# CANFD_SIC_transciever_with_WAKE_and_SLEE.net
KiCad netlist of a schematic drawn in Altium Designer
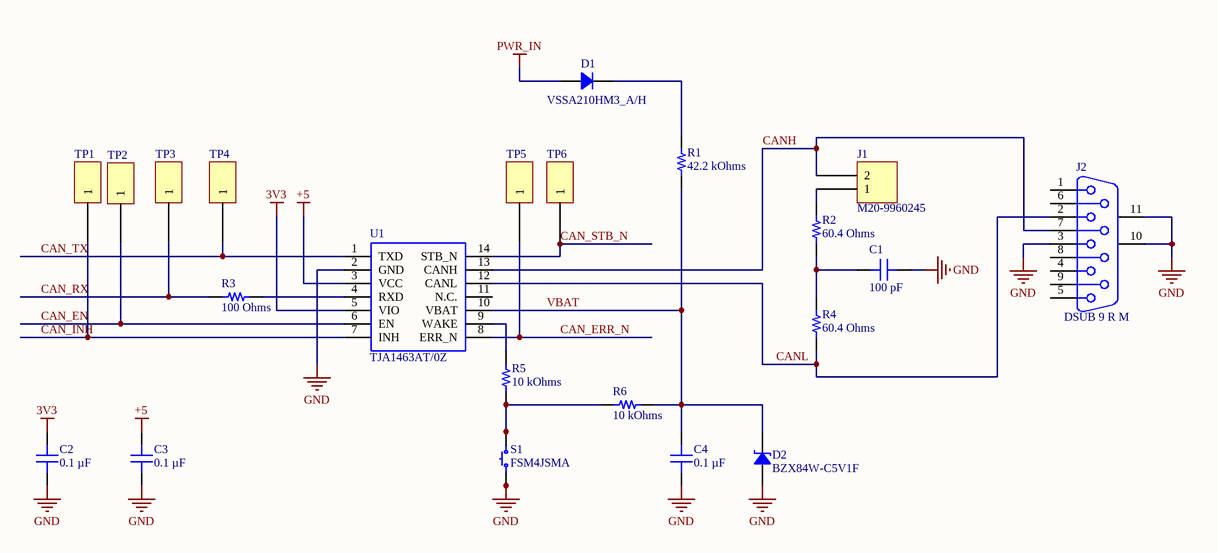
[diagram p0: CANFD_SIC_transciever_with_WAKE_and_SLEEP.SchDoc]

(export (version "E")
  (design (tool "Eeschema 10.0.6"))
  (components
    (comp (ref "C1")
      (value "100 pF")
      (footprint "CAP 0603_1608")
      (description "CAP CER 100PF 100V C0G/NPO 0603")
      (fields (field (name "PART NUMBER") "CC0603JRNPO0BN101") (field (name "MANUFACTURER") "Yageo"))
      (libsource (lib "Celestial Altium Library - altium_library") (part "Capacitor"))
    )
    (comp (ref "C2")
      (value "0.1 µF")
      (footprint "CAP 0603_1608")
      (description "CAP CER 0.1UF 16V X7R 0603")
      (fields (field (name "PART NUMBER") "CS0603KRX7R7BB104") (field (name "MANUFACTURER") "Yageo"))
      (libsource (lib "Celestial Altium Library - altium_library") (part "Capacitor"))
    )
    (comp (ref "C3")
      (value "0.1 µF")
      (footprint "CAP 0603_1608")
      (description "CAP CER 0.1UF 16V X7R 0603")
      (fields (field (name "PART NUMBER") "CS0603KRX7R7BB104") (field (name "MANUFACTURER") "Yageo"))
      (libsource (lib "Celestial Altium Library - altium_library") (part "Capacitor"))
    )
    (comp (ref "C4")
      (value "0.1 µF")
      (footprint "CAP 0603_1608")
      (description "CAP CER 0.1UF 16V X7R 0603")
      (fields (field (name "PART NUMBER") "CS0603KRX7R7BB104") (field (name "MANUFACTURER") "Yageo"))
      (libsource (lib "Celestial Altium Library - altium_library") (part "Capacitor"))
    )
    (comp (ref "D1")
      (value "VSSA210HM3_A/H")
      (footprint "DO214AC SMA")
      (description "DIODE SCHOTTKY 100V 2A DO214AC")
      (fields (field (name "MANUFACTURER") "Vishay Semiconductor Diodes Division"))
      (libsource (lib "Celestial Altium Library - altium_library") (part "Diode"))
    )
    (comp (ref "D2")
      (value "BZX84W-C5V1F")
      (footprint "DIODES SOT-323-3")
      (description "DIODE ZENER 5.1V 275MW SOT323")
      (fields (field (name "MANUFACTURER") "Nexperia USA Inc.") (field (name "TOLERANCE") "±5%"))
      (libsource (lib "Celestial Altium Library - altium_library") (part "Diode Zener"))
    )
    (comp (ref "J1")
      (value "M20-9960245")
      (footprint "HARWIN M20-9960245")
      (description "CONN HEADER R/A 2POS 2.54MM")
      (fields (field (name "MANUFACTURER") "Harwin Inc."))
      (libsource (lib "Celestial Altium Library - altium_library") (part "2 Pin"))
    )
    (comp (ref "J2")
      (value "DSUB 9 R M")
      (footprint "DSUB9_R_M")
      (description "D-Sub Standard Connectors 9P PIN RA US STAND UNC 4-40 INSERT")
      (fields (field (name "PART NUMBER") "D09P33E6RX12LF"))
      (libsource (lib "database") (part "DSUB9"))
    )
    (comp (ref "R1")
      (value "42.2 kOhms")
      (footprint "RES 0805_2012")
      (description "RES 42.2K OHM 1% 1/8W 0805")
      (fields (field (name "PART NUMBER") "CRCW080542K2FKECC") (field (name "MANUFACTURER") "Vishay Dale"))
      (libsource (lib "Celestial Altium Library - altium_library") (part "Resistor"))
    )
    (comp (ref "R2")
      (value "60.4 Ohms")
      (footprint "RES 0603_1608")
      (description "RES 60.4 OHM 1% 1/8W 0603")
      (fields
        (field (name "PART NUMBER") "RK73H1JTTD60R4F")
        (field (name "MANUFACTURER") "KOA Speer Electronics, Inc.")
      )
      (libsource (lib "Celestial Altium Library - altium_library") (part "Resistor"))
    )
    (comp (ref "R3")
      (value "100 Ohms")
      (footprint "RES 0805_2012")
      (description "RES SMD 100 OHM 1% 1/8W 0805")
      (fields
        (field (name "PART NUMBER") "ERJ-6ENF1000V")
        (field (name "MANUFACTURER") "Panasonic Electronic Components")
      )
      (libsource (lib "Celestial Altium Library - altium_library") (part "Resistor"))
    )
    (comp (ref "R4")
      (value "60.4 Ohms")
      (footprint "RES 0603_1608")
      (description "RES 60.4 OHM 1% 1/8W 0603")
      (fields
        (field (name "PART NUMBER") "RK73H1JTTD60R4F")
        (field (name "MANUFACTURER") "KOA Speer Electronics, Inc.")
      )
      (libsource (lib "Celestial Altium Library - altium_library") (part "Resistor"))
    )
    (comp (ref "R5")
      (value "10 kOhms")
      (footprint "RES 0805_2012")
      (description "RES SMD 10K OHM 1% 1/8W 0805")
      (fields (field (name "PART NUMBER") "RT0805FRE0710KL") (field (name "MANUFACTURER") "Yageo"))
      (libsource (lib "Celestial Altium Library - altium_library") (part "Resistor"))
    )
    (comp (ref "R6")
      (value "10 kOhms")
      (footprint "RES 0805_2012")
      (description "RES SMD 10K OHM 1% 1/8W 0805")
      (fields (field (name "PART NUMBER") "RT0805FRE0710KL") (field (name "MANUFACTURER") "Yageo"))
      (libsource (lib "Celestial Altium Library - altium_library") (part "Resistor"))
    )
    (comp (ref "S1")
      (value "FSM4JSMA")
      (footprint "TE FSM4JSMA")
      (description "SWITCH TACTILE SPST-NO 0.05A 24V")
      (fields (field (name "MANUFACTURER") "TE Connectivity ALCOSWITCH Switches"))
      (libsource (lib "Celestial Altium Library - altium_library") (part "SPST-NO 4 PIN"))
    )
    (comp (ref "TP1")
      (value "SSW-101-03-T-S")
      (footprint "SAMTEC SSW-101-03-T-S")
      (description "CONN RCPT 1POS TIN PCB")
      (fields (field (name "MANUFACTURER") "Samtec Inc."))
      (libsource (lib "Celestial Altium Library - altium_library") (part "1 Pin"))
    )
    (comp (ref "TP2")
      (value "SSW-101-03-T-S")
      (footprint "SAMTEC SSW-101-03-T-S")
      (description "CONN RCPT 1POS TIN PCB")
      (fields (field (name "MANUFACTURER") "Samtec Inc."))
      (libsource (lib "Celestial Altium Library - altium_library") (part "1 Pin"))
    )
    (comp (ref "TP3")
      (value "SSW-101-03-T-S")
      (footprint "SAMTEC SSW-101-03-T-S")
      (description "CONN RCPT 1POS TIN PCB")
      (fields (field (name "MANUFACTURER") "Samtec Inc."))
      (libsource (lib "Celestial Altium Library - altium_library") (part "1 Pin"))
    )
    (comp (ref "TP4")
      (value "SSW-101-03-T-S")
      (footprint "SAMTEC SSW-101-03-T-S")
      (description "CONN RCPT 1POS TIN PCB")
      (fields (field (name "MANUFACTURER") "Samtec Inc."))
      (libsource (lib "Celestial Altium Library - altium_library") (part "1 Pin"))
    )
    (comp (ref "TP5")
      (value "SSW-101-03-T-S")
      (footprint "SAMTEC SSW-101-03-T-S")
      (description "CONN RCPT 1POS TIN PCB")
      (fields (field (name "MANUFACTURER") "Samtec Inc."))
      (libsource (lib "Celestial Altium Library - altium_library") (part "1 Pin"))
    )
    (comp (ref "TP6")
      (value "SSW-101-03-T-S")
      (footprint "SAMTEC SSW-101-03-T-S")
      (description "CONN RCPT 1POS TIN PCB")
      (fields (field (name "MANUFACTURER") "Samtec Inc."))
      (libsource (lib "Celestial Altium Library - altium_library") (part "1 Pin"))
    )
    (comp (ref "U1")
      (value "TJA1463AT/0Z")
      (footprint "SOIC127P600X175-14N")
      (description "CAN SIC transciever")
      (fields (field (name "MOUSER PART NUMBER") "771-TJA1463AT/0Z"))
      (libsource (lib "database") (part "TJA1463AT_0Z"))
    )
  )
  (nets
    (net (code "1") (name "+5") (class "Default")
      (node (ref "C3") (pin "2") (pinfunction "2_2") (pintype "passive"))
      (node (ref "U1") (pin "3") (pinfunction "VCC_3") (pintype "passive"))
    )
    (net (code "2") (name "/CANH") (class "Default")
      (node (ref "J1") (pin "2") (pinfunction "2_2") (pintype "passive"))
      (node (ref "J2") (pin "7") (pinfunction "7_7") (pintype "passive"))
      (node (ref "U1") (pin "13") (pinfunction "CANH_13") (pintype "passive"))
    )
    (net (code "3") (name "/CANL") (class "Default")
      (node (ref "J2") (pin "2") (pinfunction "2_2") (pintype "passive"))
      (node (ref "R4") (pin "1") (pinfunction "1_1") (pintype "passive"))
      (node (ref "U1") (pin "12") (pinfunction "CANL_12") (pintype "passive"))
    )
    (net (code "4") (name "/CAN_EN") (class "Default")
      (node (ref "TP2") (pin "1") (pinfunction "1_1") (pintype "passive"))
      (node (ref "U1") (pin "6") (pinfunction "EN_6") (pintype "passive"))
    )
    (net (code "5") (name "/CAN_ERR_N") (class "Default")
      (node (ref "TP5") (pin "1") (pinfunction "1_1") (pintype "passive"))
      (node (ref "U1") (pin "8") (pinfunction "ERR_N_8") (pintype "passive"))
    )
    (net (code "6") (name "/CAN_INH") (class "Default")
      (node (ref "TP1") (pin "1") (pinfunction "1_1") (pintype "passive"))
      (node (ref "U1") (pin "7") (pinfunction "INH_7") (pintype "passive"))
    )
    (net (code "8") (name "/CAN_RX") (class "Default")
      (node (ref "R3") (pin "1") (pinfunction "1_1") (pintype "passive"))
      (node (ref "TP3") (pin "1") (pinfunction "1_1") (pintype "passive"))
    )
    (net (code "9") (name "/CAN_STB_N") (class "Default")
      (node (ref "TP6") (pin "1") (pinfunction "1_1") (pintype "passive"))
      (node (ref "U1") (pin "14") (pinfunction "STB_N_14") (pintype "passive"))
    )
    (net (code "10") (name "/CAN_TX") (class "Default")
      (node (ref "TP4") (pin "1") (pinfunction "1_1") (pintype "passive"))
      (node (ref "U1") (pin "1") (pinfunction "TXD_1") (pintype "passive"))
    )
    (net (code "11") (name "/VBAT") (class "Default")
      (node (ref "C4") (pin "2") (pinfunction "2_2") (pintype "passive"))
      (node (ref "D2") (pin "2") (pinfunction "2_2") (pintype "passive"))
      (node (ref "R1") (pin "1") (pinfunction "1_1") (pintype "passive"))
      (node (ref "R6") (pin "2") (pinfunction "2_2") (pintype "passive"))
      (node (ref "U1") (pin "10") (pinfunction "VBAT_10") (pintype "passive"))
    )
    (net (code "12") (name "3V3") (class "Default")
      (node (ref "C2") (pin "2") (pinfunction "2_2") (pintype "passive"))
      (node (ref "U1") (pin "5") (pinfunction "VIO_5") (pintype "passive"))
    )
    (net (code "13") (name "GND") (class "Default")
      (node (ref "C1") (pin "2") (pinfunction "2_2") (pintype "passive"))
      (node (ref "C2") (pin "1") (pinfunction "1_1") (pintype "passive"))
      (node (ref "C3") (pin "1") (pinfunction "1_1") (pintype "passive"))
      (node (ref "C4") (pin "1") (pinfunction "1_1") (pintype "passive"))
      (node (ref "D2") (pin "1") (pinfunction "1_1") (pintype "passive"))
      (node (ref "J2") (pin "10") (pinfunction "MH1_10") (pintype "passive"))
      (node (ref "J2") (pin "11") (pinfunction "MH2_11") (pintype "passive"))
      (node (ref "J2") (pin "3") (pinfunction "3_3") (pintype "passive"))
      (node (ref "S1") (pin "1") (pinfunction "1_1") (pintype "passive"))
      (node (ref "S1") (pin "2") (pinfunction "2_2") (pintype "passive"))
      (node (ref "U1") (pin "2") (pinfunction "GND_2") (pintype "passive"))
    )
    (net (code "14") (name "Net-(C1-Pad1)") (class "Default")
      (node (ref "C1") (pin "1") (pinfunction "1_1") (pintype "passive"))
      (node (ref "R2") (pin "1") (pinfunction "1_1") (pintype "passive"))
      (node (ref "R4") (pin "2") (pinfunction "2_2") (pintype "passive"))
    )
    (net (code "15") (name "Net-(D1-Pad2)") (class "Default")
      (node (ref "D1") (pin "2") (pinfunction "2_2") (pintype "passive"))
      (node (ref "R1") (pin "2") (pinfunction "2_2") (pintype "passive"))
    )
    (net (code "16") (name "Net-(J1-Pad1)") (class "Default")
      (node (ref "J1") (pin "1") (pinfunction "1_1") (pintype "passive"))
      (node (ref "R2") (pin "2") (pinfunction "2_2") (pintype "passive"))
    )
    (net (code "17") (name "Net-(R5-Pad1)") (class "Default")
      (node (ref "R5") (pin "1") (pinfunction "1_1") (pintype "passive"))
      (node (ref "R6") (pin "1") (pinfunction "1_1") (pintype "passive"))
      (node (ref "S1") (pin "3") (pinfunction "3_3") (pintype "passive"))
      (node (ref "S1") (pin "4") (pinfunction "4_4") (pintype "passive"))
    )
    (net (code "18") (name "Net-(U1-RXD)") (class "Default")
      (node (ref "R3") (pin "2") (pinfunction "2_2") (pintype "passive"))
      (node (ref "U1") (pin "4") (pinfunction "RXD_4") (pintype "passive"))
    )
    (net (code "19") (name "Net-(U1-WAKE)") (class "Default")
      (node (ref "R5") (pin "2") (pinfunction "2_2") (pintype "passive"))
      (node (ref "U1") (pin "9") (pinfunction "WAKE_9") (pintype "passive"))
    )
    (net (code "20") (name "PWR_IN") (class "Default")
      (node (ref "D1") (pin "1") (pinfunction "1_1") (pintype "passive"))
    )
    (net (code "21") (name "unconnected-(J2-Pad1)") (class "Default")
      (node (ref "J2") (pin "1") (pinfunction "1_1") (pintype "passive"))
    )
    (net (code "22") (name "unconnected-(J2-Pad4)") (class "Default")
      (node (ref "J2") (pin "4") (pinfunction "4_4") (pintype "passive"))
    )
    (net (code "23") (name "unconnected-(J2-Pad5)") (class "Default")
      (node (ref "J2") (pin "5") (pinfunction "5_5") (pintype "passive"))
    )
    (net (code "24") (name "unconnected-(J2-Pad6)") (class "Default")
      (node (ref "J2") (pin "6") (pinfunction "6_6") (pintype "passive"))
    )
    (net (code "25") (name "unconnected-(J2-Pad8)") (class "Default")
      (node (ref "J2") (pin "8") (pinfunction "8_8") (pintype "passive"))
    )
    (net (code "26") (name "unconnected-(J2-Pad9)") (class "Default")
      (node (ref "J2") (pin "9") (pinfunction "9_9") (pintype "passive"))
    )
    (net (code "27") (name "unconnected-(U1-N.C.-Pad11)") (class "Default")
      (node (ref "U1") (pin "11") (pinfunction "N.C._11") (pintype "passive"))
    )
  )
)
